# Sheet1.net
KiCad netlist of a schematic drawn in Altium Designer
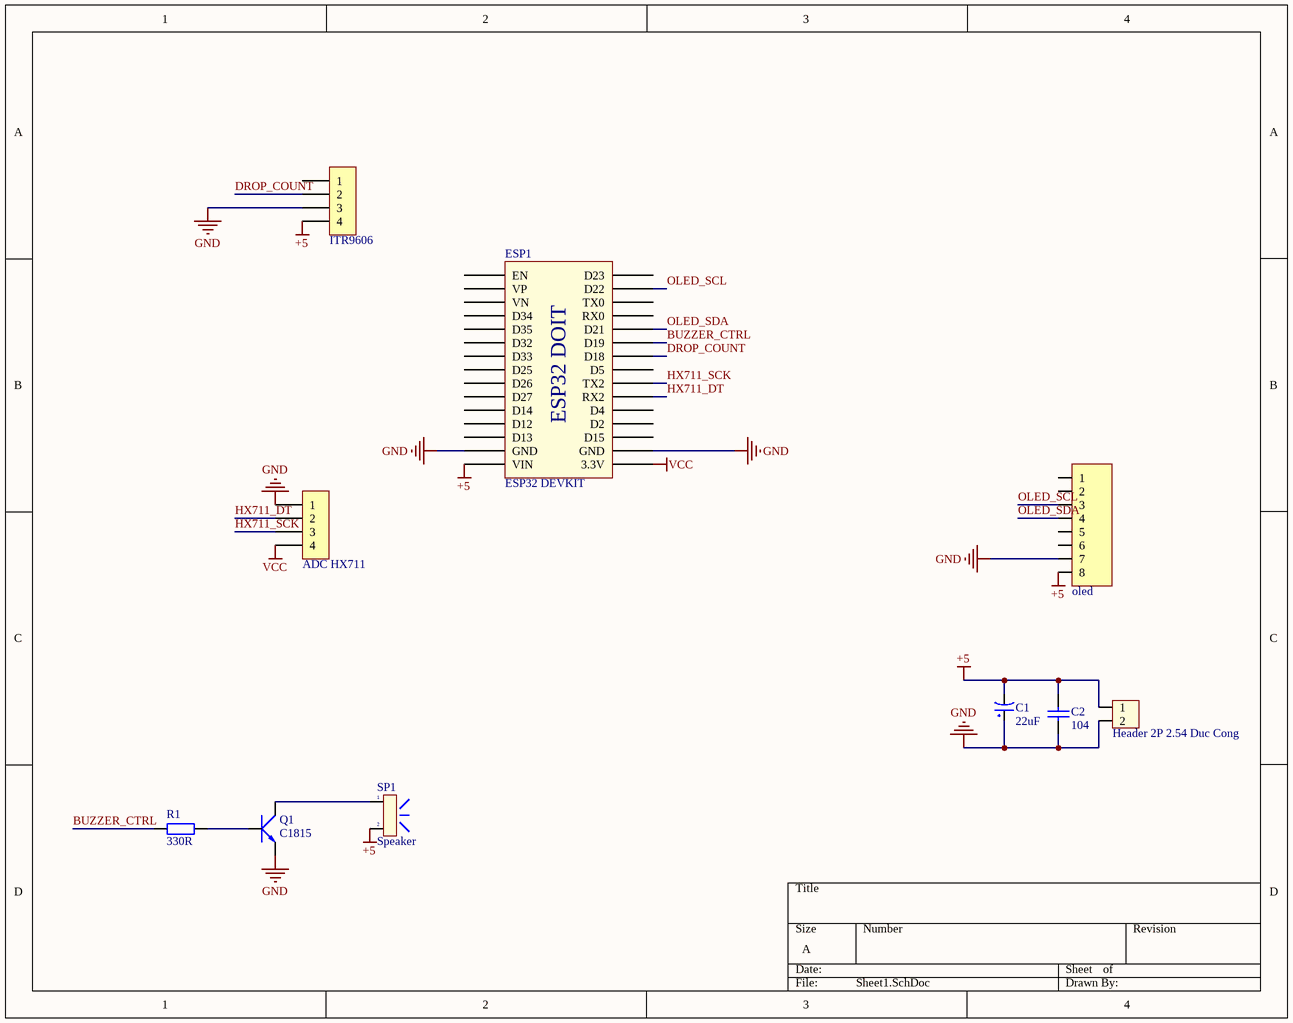
[diagram p0: Sheet1.SchDoc]

(export (version "E")
  (design (tool "Eeschema 10.0.6"))
  (components
    (comp (ref "C1")
      (value "22uF")
      (footprint "tu hoa 4mm")
      (description "Cắm")
      (libsource (lib "AltiumLib_KhueNguyenCreator") (part "Tu Hoa 22uF 16V 4x7"))
    )
    (comp (ref "C2")
      (value "104")
      (footprint "tu gom")
      (description "Cắm")
      (libsource (lib "AltiumLib_KhueNguyenCreator") (part "Tu gom 104 50V"))
    )
    (comp (ref "ESP1")
      (value "ESP32 DEVKIT")
      (footprint "ESP32 WROOM 32 KIT")
      (libsource (lib "AltiumLib_KhueNguyenCreator") (part "ESP32 WROOM 32 KIT"))
    )
    (comp (ref "H1")
      (value "ITR9606")
      (footprint "Header 4P DC 2.54")
      (description "Cắm")
      (libsource (lib "AltiumLib_KhueNguyenCreator") (part "Header 4P 2.54 Duc Cong"))
    )
    (comp (ref "H2")
      (value "ADC HX711")
      (footprint "Header 4P DC 2.54")
      (description "Cắm")
      (libsource (lib "AltiumLib_KhueNguyenCreator") (part "Header 4P 2.54 Duc Cong"))
    )
    (comp (ref "H3")
      (value "Header 2P 2.54 Duc Cong")
      (footprint "Header 2P DC 2.54")
      (description "Cắm")
      (libsource (lib "AltiumLib_KhueNguyenCreator") (part "Header 2P 2.54 Duc Cong"))
    )
    (comp (ref "JP 1x8 2.54")
      (value "oled")
      (footprint "JP 1x8 DT")
      (description "Cắm")
      (libsource (lib "AltiumLib_KhueNguyenCreator") (part "JP 1x8 2.54 Duc Thang"))
    )
    (comp (ref "Q1")
      (value "C1815")
      (footprint "TO92")
      (description "NPN transistor")
      (libsource (lib "AltiumLib_KhueNguyenCreator") (part "Trans C1815 DIP"))
    )
    (comp (ref "R1")
      (value "330R")
      (footprint "tro vach 1/4w")
      (description "Cắm")
      (libsource (lib "AltiumLib_KhueNguyenCreator") (part "Tro Vach 1/4W 1% 330R"))
    )
    (comp (ref "SP1")
      (value "Speaker")
      (footprint "SPK")
      (description "Speaker Chip")
      (libsource (lib "4.Thuvien3D") (part "SPK"))
    )
  )
  (nets
    (net (code "1") (name "+5") (class "Default")
      (node (ref "C1") (pin "2") (pinfunction "2_2") (pintype "passive"))
      (node (ref "C2") (pin "1") (pinfunction "1_1") (pintype "passive"))
      (node (ref "ESP1") (pin "15") (pinfunction "VIN_15") (pintype "passive"))
      (node (ref "H1") (pin "4") (pinfunction "4_4") (pintype "passive"))
      (node (ref "H3") (pin "1") (pinfunction "1_1") (pintype "passive"))
      (node (ref "JP 1x8 2.54") (pin "8") (pinfunction "8_8") (pintype "passive"))
      (node (ref "SP1") (pin "2") (pinfunction "2_2") (pintype "passive"))
    )
    (net (code "2") (name "/BUZZER_CTRL") (class "Default")
      (node (ref "ESP1") (pin "25") (pinfunction "D19_25") (pintype "passive"))
      (node (ref "R1") (pin "1") (pinfunction "1_1") (pintype "passive"))
    )
    (net (code "3") (name "/DROP_COUNT") (class "Default")
      (node (ref "ESP1") (pin "24") (pinfunction "D18_24") (pintype "passive"))
      (node (ref "H1") (pin "2") (pinfunction "2_2") (pintype "passive"))
    )
    (net (code "4") (name "/HX711_DT") (class "Default")
      (node (ref "ESP1") (pin "21") (pinfunction "RX2_21") (pintype "passive"))
      (node (ref "H2") (pin "2") (pinfunction "2_2") (pintype "passive"))
    )
    (net (code "5") (name "/HX711_SCK") (class "Default")
      (node (ref "ESP1") (pin "22") (pinfunction "TX2_22") (pintype "passive"))
      (node (ref "H2") (pin "3") (pinfunction "3_3") (pintype "passive"))
    )
    (net (code "6") (name "/OLED_SCL") (class "Default")
      (node (ref "ESP1") (pin "29") (pinfunction "D22_29") (pintype "passive"))
      (node (ref "JP 1x8 2.54") (pin "3") (pinfunction "3_3") (pintype "passive"))
    )
    (net (code "7") (name "/OLED_SDA") (class "Default")
      (node (ref "ESP1") (pin "26") (pinfunction "D21_26") (pintype "passive"))
      (node (ref "JP 1x8 2.54") (pin "4") (pinfunction "4_4") (pintype "passive"))
    )
    (net (code "8") (name "GND") (class "Default")
      (node (ref "C1") (pin "1") (pinfunction "1_1") (pintype "passive"))
      (node (ref "C2") (pin "2") (pinfunction "2_2") (pintype "passive"))
      (node (ref "ESP1") (pin "14") (pinfunction "GND_14") (pintype "passive"))
      (node (ref "ESP1") (pin "17") (pinfunction "GND_17") (pintype "passive"))
      (node (ref "H1") (pin "3") (pinfunction "3_3") (pintype "passive"))
      (node (ref "H2") (pin "1") (pinfunction "1_1") (pintype "passive"))
      (node (ref "H3") (pin "2") (pinfunction "2_2") (pintype "passive"))
      (node (ref "JP 1x8 2.54") (pin "7") (pinfunction "7_7") (pintype "passive"))
      (node (ref "Q1") (pin "1") (pinfunction "E_1") (pintype "passive"))
    )
    (net (code "9") (name "Net-(Q1-B)") (class "Default")
      (node (ref "Q1") (pin "3") (pinfunction "B_3") (pintype "passive"))
      (node (ref "R1") (pin "2") (pinfunction "2_2") (pintype "passive"))
    )
    (net (code "10") (name "Net-(Q1-C)") (class "Default")
      (node (ref "Q1") (pin "2") (pinfunction "C_2") (pintype "passive"))
      (node (ref "SP1") (pin "1") (pinfunction "1_1") (pintype "passive"))
    )
    (net (code "11") (name "VCC") (class "Default")
      (node (ref "ESP1") (pin "16") (pinfunction "3.3V_16") (pintype "passive"))
      (node (ref "H2") (pin "4") (pinfunction "4_4") (pintype "passive"))
    )
    (net (code "12") (name "unconnected-(ESP1-D2-Pad19)") (class "Default")
      (node (ref "ESP1") (pin "19") (pinfunction "D2_19") (pintype "passive"))
    )
    (net (code "13") (name "unconnected-(ESP1-D4-Pad20)") (class "Default")
      (node (ref "ESP1") (pin "20") (pinfunction "D4_20") (pintype "passive"))
    )
    (net (code "14") (name "unconnected-(ESP1-D5-Pad23)") (class "Default")
      (node (ref "ESP1") (pin "23") (pinfunction "D5_23") (pintype "passive"))
    )
    (net (code "15") (name "unconnected-(ESP1-D12-Pad12)") (class "Default")
      (node (ref "ESP1") (pin "12") (pinfunction "D12_12") (pintype "passive"))
    )
    (net (code "16") (name "unconnected-(ESP1-D13-Pad13)") (class "Default")
      (node (ref "ESP1") (pin "13") (pinfunction "D13_13") (pintype "passive"))
    )
    (net (code "17") (name "unconnected-(ESP1-D14-Pad11)") (class "Default")
      (node (ref "ESP1") (pin "11") (pinfunction "D14_11") (pintype "passive"))
    )
    (net (code "18") (name "unconnected-(ESP1-D15-Pad18)") (class "Default")
      (node (ref "ESP1") (pin "18") (pinfunction "D15_18") (pintype "passive"))
    )
    (net (code "19") (name "unconnected-(ESP1-D23-Pad30)") (class "Default")
      (node (ref "ESP1") (pin "30") (pinfunction "D23_30") (pintype "passive"))
    )
    (net (code "20") (name "unconnected-(ESP1-D25-Pad8)") (class "Default")
      (node (ref "ESP1") (pin "8") (pinfunction "D25_8") (pintype "passive"))
    )
    (net (code "21") (name "unconnected-(ESP1-D26-Pad9)") (class "Default")
      (node (ref "ESP1") (pin "9") (pinfunction "D26_9") (pintype "passive"))
    )
    (net (code "22") (name "unconnected-(ESP1-D27-Pad10)") (class "Default")
      (node (ref "ESP1") (pin "10") (pinfunction "D27_10") (pintype "passive"))
    )
    (net (code "23") (name "unconnected-(ESP1-D32-Pad6)") (class "Default")
      (node (ref "ESP1") (pin "6") (pinfunction "D32_6") (pintype "passive"))
    )
    (net (code "24") (name "unconnected-(ESP1-D33-Pad7)") (class "Default")
      (node (ref "ESP1") (pin "7") (pinfunction "D33_7") (pintype "passive"))
    )
    (net (code "25") (name "unconnected-(ESP1-D34-Pad4)") (class "Default")
      (node (ref "ESP1") (pin "4") (pinfunction "D34_4") (pintype "passive"))
    )
    (net (code "26") (name "unconnected-(ESP1-D35-Pad5)") (class "Default")
      (node (ref "ESP1") (pin "5") (pinfunction "D35_5") (pintype "passive"))
    )
    (net (code "27") (name "unconnected-(ESP1-EN-Pad1)") (class "Default")
      (node (ref "ESP1") (pin "1") (pinfunction "EN_1") (pintype "passive"))
    )
    (net (code "28") (name "unconnected-(ESP1-RX0-Pad27)") (class "Default")
      (node (ref "ESP1") (pin "27") (pinfunction "RX0_27") (pintype "passive"))
    )
    (net (code "29") (name "unconnected-(ESP1-TX0-Pad28)") (class "Default")
      (node (ref "ESP1") (pin "28") (pinfunction "TX0_28") (pintype "passive"))
    )
    (net (code "30") (name "unconnected-(ESP1-VN-Pad3)") (class "Default")
      (node (ref "ESP1") (pin "3") (pinfunction "VN_3") (pintype "passive"))
    )
    (net (code "31") (name "unconnected-(ESP1-VP-Pad2)") (class "Default")
      (node (ref "ESP1") (pin "2") (pinfunction "VP_2") (pintype "passive"))
    )
    (net (code "32") (name "unconnected-(H1-Pad1)") (class "Default")
      (node (ref "H1") (pin "1") (pinfunction "1_1") (pintype "passive"))
    )
    (net (code "33") (name "unconnected-(JP 1x8 2.54-Pad1)") (class "Default")
      (node (ref "JP 1x8 2.54") (pin "1") (pinfunction "1_1") (pintype "passive"))
    )
    (net (code "34") (name "unconnected-(JP 1x8 2.54-Pad2)") (class "Default")
      (node (ref "JP 1x8 2.54") (pin "2") (pinfunction "2_2") (pintype "passive"))
    )
    (net (code "35") (name "unconnected-(JP 1x8 2.54-Pad5)") (class "Default")
      (node (ref "JP 1x8 2.54") (pin "5") (pinfunction "5_5") (pintype "passive"))
    )
    (net (code "36") (name "unconnected-(JP 1x8 2.54-Pad6)") (class "Default")
      (node (ref "JP 1x8 2.54") (pin "6") (pinfunction "6_6") (pintype "passive"))
    )
  )
)
